# battery_regulator.net
KiCad netlist of a schematic drawn in Altium Designer
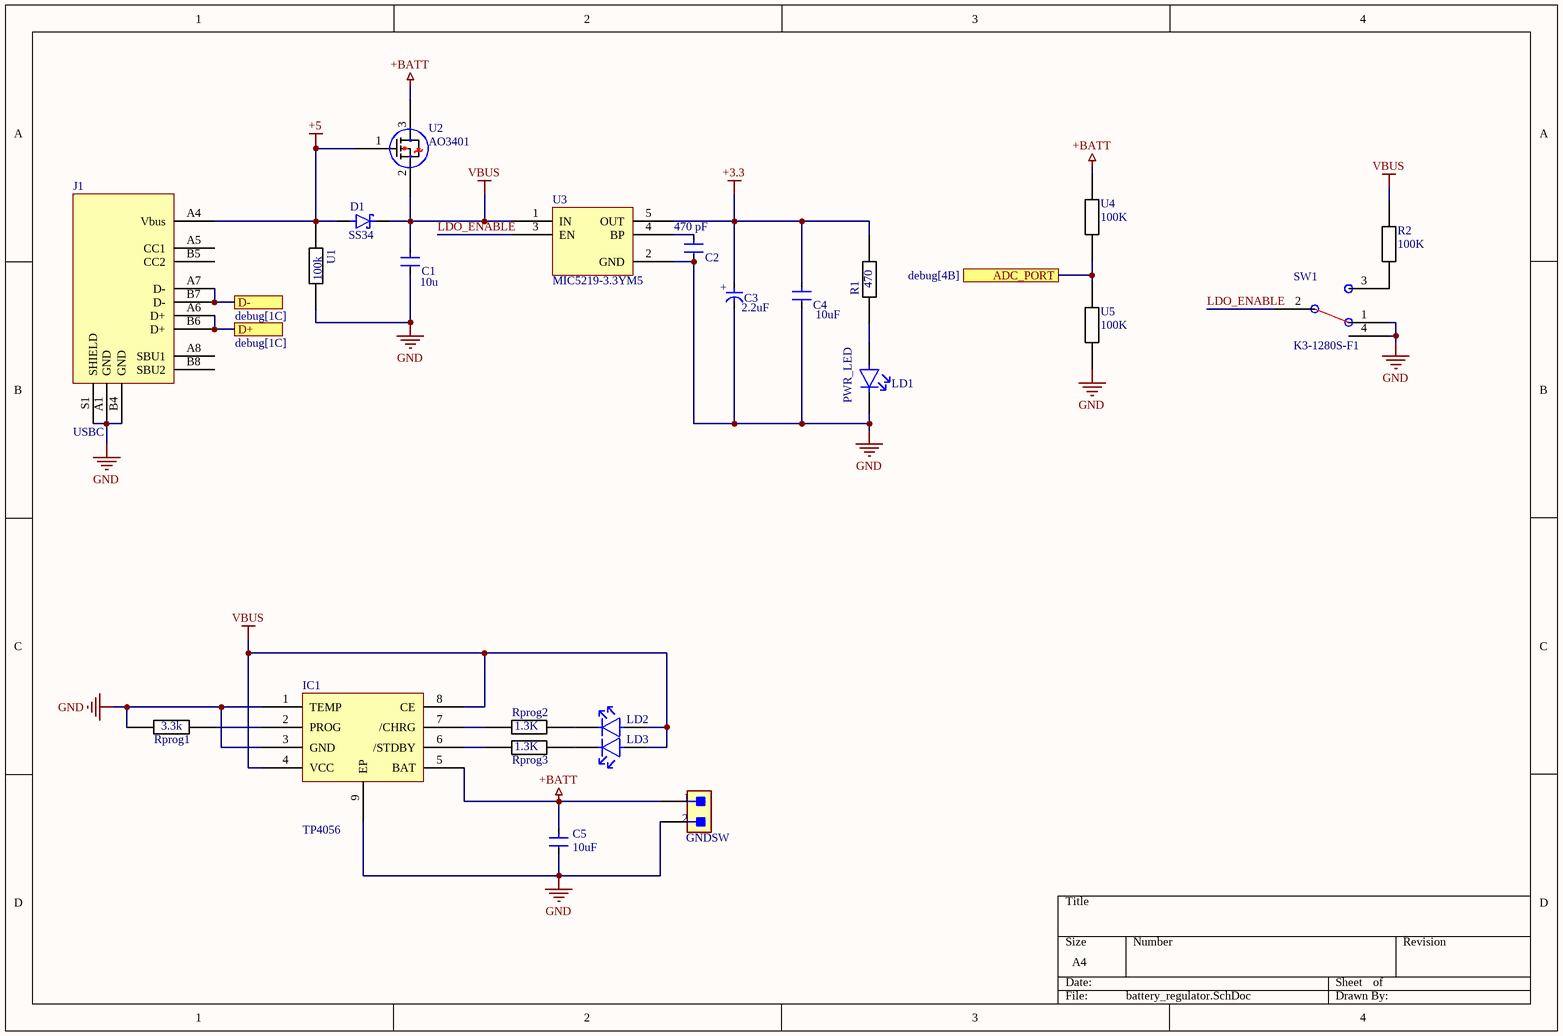
[diagram p0: battery_regulator.SchDoc]

(export (version "E")
  (design (tool "Eeschema 10.0.6"))
  (components
    (comp (ref "C1")
      (value "10u")
      (footprint "res0805ph")
      (fields (field (name "TOLERANCE") "20%"))
      (libsource (lib "LibraryTechnologie (1)") (part "CER Capacitor_1"))
    )
    (comp (ref "C2")
      (value "470 pF")
      (footprint "res0805ph")
      (fields (field (name "TOLERANCE") "20%"))
      (libsource (lib "LibraryTechnologie (1)") (part "CER Capacitor_1"))
    )
    (comp (ref "C3")
      (value "2.2uF")
      (footprint "res0805ph")
      (description "47uF 6.3V  ±20% 1.1Ω 2917  SMD Tantalum Capacitor")
      (fields (field (name "TOLERANCE") "20%"))
      (libsource (lib "LibraryTechnologie (1)") (part "Elco+tantaal_1"))
    )
    (comp (ref "C4")
      (value "10uF")
      (footprint "res0805ph")
      (fields (field (name "TOLERANCE") "20%"))
      (libsource (lib "LibraryTechnologie (1)") (part "CER Capacitor_1"))
    )
    (comp (ref "C5")
      (value "10uF")
      (footprint "res0805ph")
      (fields (field (name "TOLERANCE") "20%"))
      (libsource (lib "LibraryTechnologie (1)") (part "CER Capacitor_1"))
    )
    (comp (ref "D1") (value "SS34") (footprint "DIOM7959X265N") (libsource (lib "Dronesch") (part "SS34")))
    (comp (ref "GNDSW")
      (value "TMM-102-02-L-S")
      (footprint "JST_B2B-XH-A_(LF)(SN)")
      (description "CONN HEADER VERT 2POS 2MM")
      (libsource (lib "LibraryTechnologie (1)") (part "Connector 1x2_1"))
    )
    (comp (ref "IC1")
      (value "TP4056")
      (footprint "SOP127P600X175-9N")
      (libsource (lib "LibraryTechnologie (1)") (part "TP4056"))
    )
    (comp (ref "J1")
      (value "USBC")
      (footprint "SHENZHEN-CHUANGQIN-TECHNOLOGY_CQ-USB-C16PSMT01")
      (libsource (lib "Dronesch") (part "USBC"))
    )
    (comp (ref "LD1")
      (value "PWR_LED")
      (footprint "res0805ph")
      (description "LED GREEN CLEAR CHIP SMD")
      (libsource (lib "LibraryTechnologie (1)") (part "LED_1"))
    )
    (comp (ref "LD2")
      (value "APT1608ZGCK")
      (footprint "res0805ph")
      (description "LED GREEN CLEAR CHIP SMD")
      (libsource (lib "LibraryTechnologie (1)") (part "LED_1"))
    )
    (comp (ref "LD3")
      (value "APT1608ZGCK")
      (footprint "res0805ph")
      (description "LED GREEN CLEAR CHIP SMD")
      (libsource (lib "LibraryTechnologie (1)") (part "LED_1"))
    )
    (comp (ref "R1")
      (value "470")
      (footprint "res0805ph")
      (description "RES SMD 5.9K OHM 1% 1/4W 1206")
      (fields
        (field (name "OCTOPART") "https://octopart.com/ac1206fr-075k9l-yageo-30511161")
        (field (name "MANUFACTURER") "Yageo")
      )
      (libsource (lib "LibraryTechnologie (1)") (part "Weerstand_1"))
    )
    (comp (ref "R2")
      (value "100K")
      (footprint "res0805ph")
      (description "RES SMD 5.9K OHM 1% 1/4W 1206")
      (fields
        (field (name "OCTOPART") "https://octopart.com/ac1206fr-075k9l-yageo-30511161")
        (field (name "MANUFACTURER") "Yageo")
      )
      (libsource (lib "LibraryTechnologie (1)") (part "Weerstand_1"))
    )
    (comp (ref "Rprog1")
      (value "3.3k")
      (footprint "res0805ph")
      (description "RES SMD 5.9K OHM 1% 1/4W 1206")
      (fields
        (field (name "OCTOPART") "https://octopart.com/ac1206fr-075k9l-yageo-30511161")
        (field (name "MANUFACTURER") "Yageo")
      )
      (libsource (lib "LibraryTechnologie (1)") (part "Weerstand_1"))
    )
    (comp (ref "Rprog2")
      (value "1.3K")
      (footprint "res0805ph")
      (description "RES SMD 5.9K OHM 1% 1/4W 1206")
      (fields
        (field (name "OCTOPART") "https://octopart.com/ac1206fr-075k9l-yageo-30511161")
        (field (name "MANUFACTURER") "Yageo")
      )
      (libsource (lib "LibraryTechnologie (1)") (part "Weerstand_1"))
    )
    (comp (ref "Rprog3")
      (value "1.3K")
      (footprint "res0805ph")
      (description "RES SMD 5.9K OHM 1% 1/4W 1206")
      (fields
        (field (name "OCTOPART") "https://octopart.com/ac1206fr-075k9l-yageo-30511161")
        (field (name "MANUFACTURER") "Yageo")
      )
      (libsource (lib "LibraryTechnologie (1)") (part "Weerstand_1"))
    )
    (comp (ref "SW1")
      (value "K3-1280S-F1")
      (footprint "SW-SMD_K3-1280S-K1")
      (libsource (lib "Dronesch") (part "Switch"))
    )
    (comp (ref "U1")
      (value "100k")
      (footprint "res0805ph")
      (description "RES SMD 5.9K OHM 1% 1/4W 1206")
      (fields
        (field (name "OCTOPART") "https://octopart.com/ac1206fr-075k9l-yageo-30511161")
        (field (name "MANUFACTURER") "Yageo")
      )
      (libsource (lib "LibraryTechnologie (1)") (part "Weerstand_1"))
    )
    (comp (ref "U2") (value "AO3401") (footprint "SOT23-3") (libsource (lib "Dronesch") (part "Transistor")))
    (comp (ref "U3")
      (value "MIC5219-3.3YM5")
      (footprint "FP-SOT23-5LD-PL-1-IPC_C")
      (libsource (lib "Dronesch") (part "MIC5219-3.3YM5"))
    )
    (comp (ref "U4")
      (value "100K")
      (footprint "res0805ph")
      (description "RES SMD 5.9K OHM 1% 1/4W 1206")
      (fields
        (field (name "OCTOPART") "https://octopart.com/ac1206fr-075k9l-yageo-30511161")
        (field (name "MANUFACTURER") "Yageo")
      )
      (libsource (lib "LibraryTechnologie (1)") (part "Weerstand_1"))
    )
    (comp (ref "U5")
      (value "100K")
      (footprint "res0805ph")
      (description "RES SMD 5.9K OHM 1% 1/4W 1206")
      (fields
        (field (name "OCTOPART") "https://octopart.com/ac1206fr-075k9l-yageo-30511161")
        (field (name "MANUFACTURER") "Yageo")
      )
      (libsource (lib "LibraryTechnologie (1)") (part "Weerstand_1"))
    )
  )
  (nets
    (net (code "1") (name "+3.3") (class "Default")
      (node (ref "C3") (pin "2") (pinfunction "A_2") (pintype "passive"))
      (node (ref "C4") (pin "1") (pinfunction "1_1") (pintype "passive"))
      (node (ref "R1") (pin "2") (pinfunction "2_2") (pintype "passive"))
      (node (ref "U3") (pin "5") (pinfunction "OUT_5") (pintype "passive"))
    )
    (net (code "2") (name "+5") (class "Default")
      (node (ref "D1") (pin "A") (pinfunction "A_A") (pintype "passive"))
      (node (ref "J1") (pin "A4") (pinfunction "Vbus_A4") (pintype "passive"))
      (node (ref "U1") (pin "2") (pinfunction "2_2") (pintype "passive"))
      (node (ref "U2") (pin "1") (pinfunction "1_1") (pintype "passive"))
    )
    (net (code "3") (name "+BATT") (class "Default")
      (node (ref "C5") (pin "1") (pinfunction "1_1") (pintype "passive"))
      (node (ref "GNDSW") (pin "1") (pinfunction "1_1") (pintype "passive"))
      (node (ref "IC1") (pin "5") (pinfunction "BAT_5") (pintype "passive"))
      (node (ref "U2") (pin "3") (pinfunction "3_3") (pintype "passive"))
      (node (ref "U4") (pin "1") (pinfunction "1_1") (pintype "passive"))
    )
    (net (code "4") (name "/ADC_PORT") (class "Default")
      (node (ref "U4") (pin "2") (pinfunction "2_2") (pintype "passive"))
      (node (ref "U5") (pin "1") (pinfunction "1_1") (pintype "passive"))
    )
    (net (code "5") (name "/D+") (class "Default")
      (node (ref "J1") (pin "A6") (pinfunction "D+_A6") (pintype "passive"))
      (node (ref "J1") (pin "B6") (pinfunction "D+_B6") (pintype "passive"))
    )
    (net (code "6") (name "/D-") (class "Default")
      (node (ref "J1") (pin "A7") (pinfunction "D-_A7") (pintype "passive"))
      (node (ref "J1") (pin "B7") (pinfunction "D-_B7") (pintype "passive"))
    )
    (net (code "7") (name "/LDO_ENABLE") (class "Default")
      (node (ref "SW1") (pin "2") (pinfunction "21_2") (pintype "passive"))
      (node (ref "U3") (pin "3") (pinfunction "EN_3") (pintype "passive"))
    )
    (net (code "8") (name "GND") (class "Default")
      (node (ref "C1") (pin "2") (pinfunction "2_2") (pintype "passive"))
      (node (ref "C2") (pin "2") (pinfunction "2_2") (pintype "passive"))
      (node (ref "C3") (pin "1") (pinfunction "C_1") (pintype "passive"))
      (node (ref "C4") (pin "2") (pinfunction "2_2") (pintype "passive"))
      (node (ref "C5") (pin "2") (pinfunction "2_2") (pintype "passive"))
      (node (ref "GNDSW") (pin "2") (pinfunction "2_2") (pintype "passive"))
      (node (ref "IC1") (pin "1") (pinfunction "TEMP_1") (pintype "passive"))
      (node (ref "IC1") (pin "3") (pinfunction "GND_3") (pintype "passive"))
      (node (ref "IC1") (pin "9") (pinfunction "EP_9") (pintype "passive"))
      (node (ref "J1") (pin "A1") (pinfunction "GND_A1") (pintype "passive"))
      (node (ref "J1") (pin "B4") (pinfunction "GND_B4") (pintype "passive"))
      (node (ref "J1") (pin "S1") (pinfunction "SHIELD_S1") (pintype "passive"))
      (node (ref "LD1") (pin "1") (pinfunction "C_1") (pintype "passive"))
      (node (ref "Rprog1") (pin "2") (pinfunction "2_2") (pintype "passive"))
      (node (ref "SW1") (pin "1") (pinfunction "23_1") (pintype "passive"))
      (node (ref "SW1") (pin "4") (pinfunction "24_4") (pintype "passive"))
      (node (ref "U1") (pin "1") (pinfunction "1_1") (pintype "passive"))
      (node (ref "U3") (pin "2") (pinfunction "GND_2") (pintype "passive"))
      (node (ref "U5") (pin "2") (pinfunction "2_2") (pintype "passive"))
    )
    (net (code "9") (name "Net-(IC1-PROG)") (class "Default")
      (node (ref "IC1") (pin "2") (pinfunction "PROG_2") (pintype "passive"))
      (node (ref "Rprog1") (pin "1") (pinfunction "1_1") (pintype "passive"))
    )
    (net (code "10") (name "Net-(IC1-{slash}CHRG)") (class "Default")
      (node (ref "IC1") (pin "7") (pinfunction "/CHRG_7") (pintype "passive"))
      (node (ref "Rprog2") (pin "2") (pinfunction "2_2") (pintype "passive"))
    )
    (net (code "11") (name "Net-(IC1-{slash}STDBY)") (class "Default")
      (node (ref "IC1") (pin "6") (pinfunction "/STDBY_6") (pintype "passive"))
      (node (ref "Rprog3") (pin "2") (pinfunction "2_2") (pintype "passive"))
    )
    (net (code "12") (name "Net-(LD1-A)") (class "Default")
      (node (ref "LD1") (pin "2") (pinfunction "A_2") (pintype "passive"))
      (node (ref "R1") (pin "1") (pinfunction "1_1") (pintype "passive"))
    )
    (net (code "13") (name "Net-(LD2-C)") (class "Default")
      (node (ref "LD2") (pin "1") (pinfunction "C_1") (pintype "passive"))
      (node (ref "Rprog2") (pin "1") (pinfunction "1_1") (pintype "passive"))
    )
    (net (code "14") (name "Net-(LD3-C)") (class "Default")
      (node (ref "LD3") (pin "1") (pinfunction "C_1") (pintype "passive"))
      (node (ref "Rprog3") (pin "1") (pinfunction "1_1") (pintype "passive"))
    )
    (net (code "15") (name "Net-(SW1-22)") (class "Default")
      (node (ref "R2") (pin "2") (pinfunction "2_2") (pintype "passive"))
      (node (ref "SW1") (pin "3") (pinfunction "22_3") (pintype "passive"))
    )
    (net (code "16") (name "Net-(U3-BP)") (class "Default")
      (node (ref "C2") (pin "1") (pinfunction "1_1") (pintype "passive"))
      (node (ref "U3") (pin "4") (pinfunction "BP_4") (pintype "passive"))
    )
    (net (code "17") (name "VBUS") (class "Default")
      (node (ref "C1") (pin "1") (pinfunction "1_1") (pintype "passive"))
      (node (ref "D1") (pin "C") (pinfunction "K_C") (pintype "passive"))
      (node (ref "IC1") (pin "4") (pinfunction "VCC_4") (pintype "passive"))
      (node (ref "IC1") (pin "8") (pinfunction "CE_8") (pintype "passive"))
      (node (ref "LD2") (pin "2") (pinfunction "A_2") (pintype "passive"))
      (node (ref "LD3") (pin "2") (pinfunction "A_2") (pintype "passive"))
      (node (ref "R2") (pin "1") (pinfunction "1_1") (pintype "passive"))
      (node (ref "U2") (pin "2") (pinfunction "2_2") (pintype "passive"))
      (node (ref "U3") (pin "1") (pinfunction "IN_1") (pintype "passive"))
    )
    (net (code "18") (name "unconnected-(J1-CC1-PadA5)") (class "Default")
      (node (ref "J1") (pin "A5") (pinfunction "CC1_A5") (pintype "passive"))
    )
    (net (code "19") (name "unconnected-(J1-CC2-PadB5)") (class "Default")
      (node (ref "J1") (pin "B5") (pinfunction "CC2_B5") (pintype "passive"))
    )
    (net (code "20") (name "unconnected-(J1-SBU1-PadA8)") (class "Default")
      (node (ref "J1") (pin "A8") (pinfunction "SBU1_A8") (pintype "passive"))
    )
    (net (code "21") (name "unconnected-(J1-SBU2-PadB8)") (class "Default")
      (node (ref "J1") (pin "B8") (pinfunction "SBU2_B8") (pintype "passive"))
    )
  )
)
